# dimmer.net
KiCad netlist of a schematic drawn in EAGLE
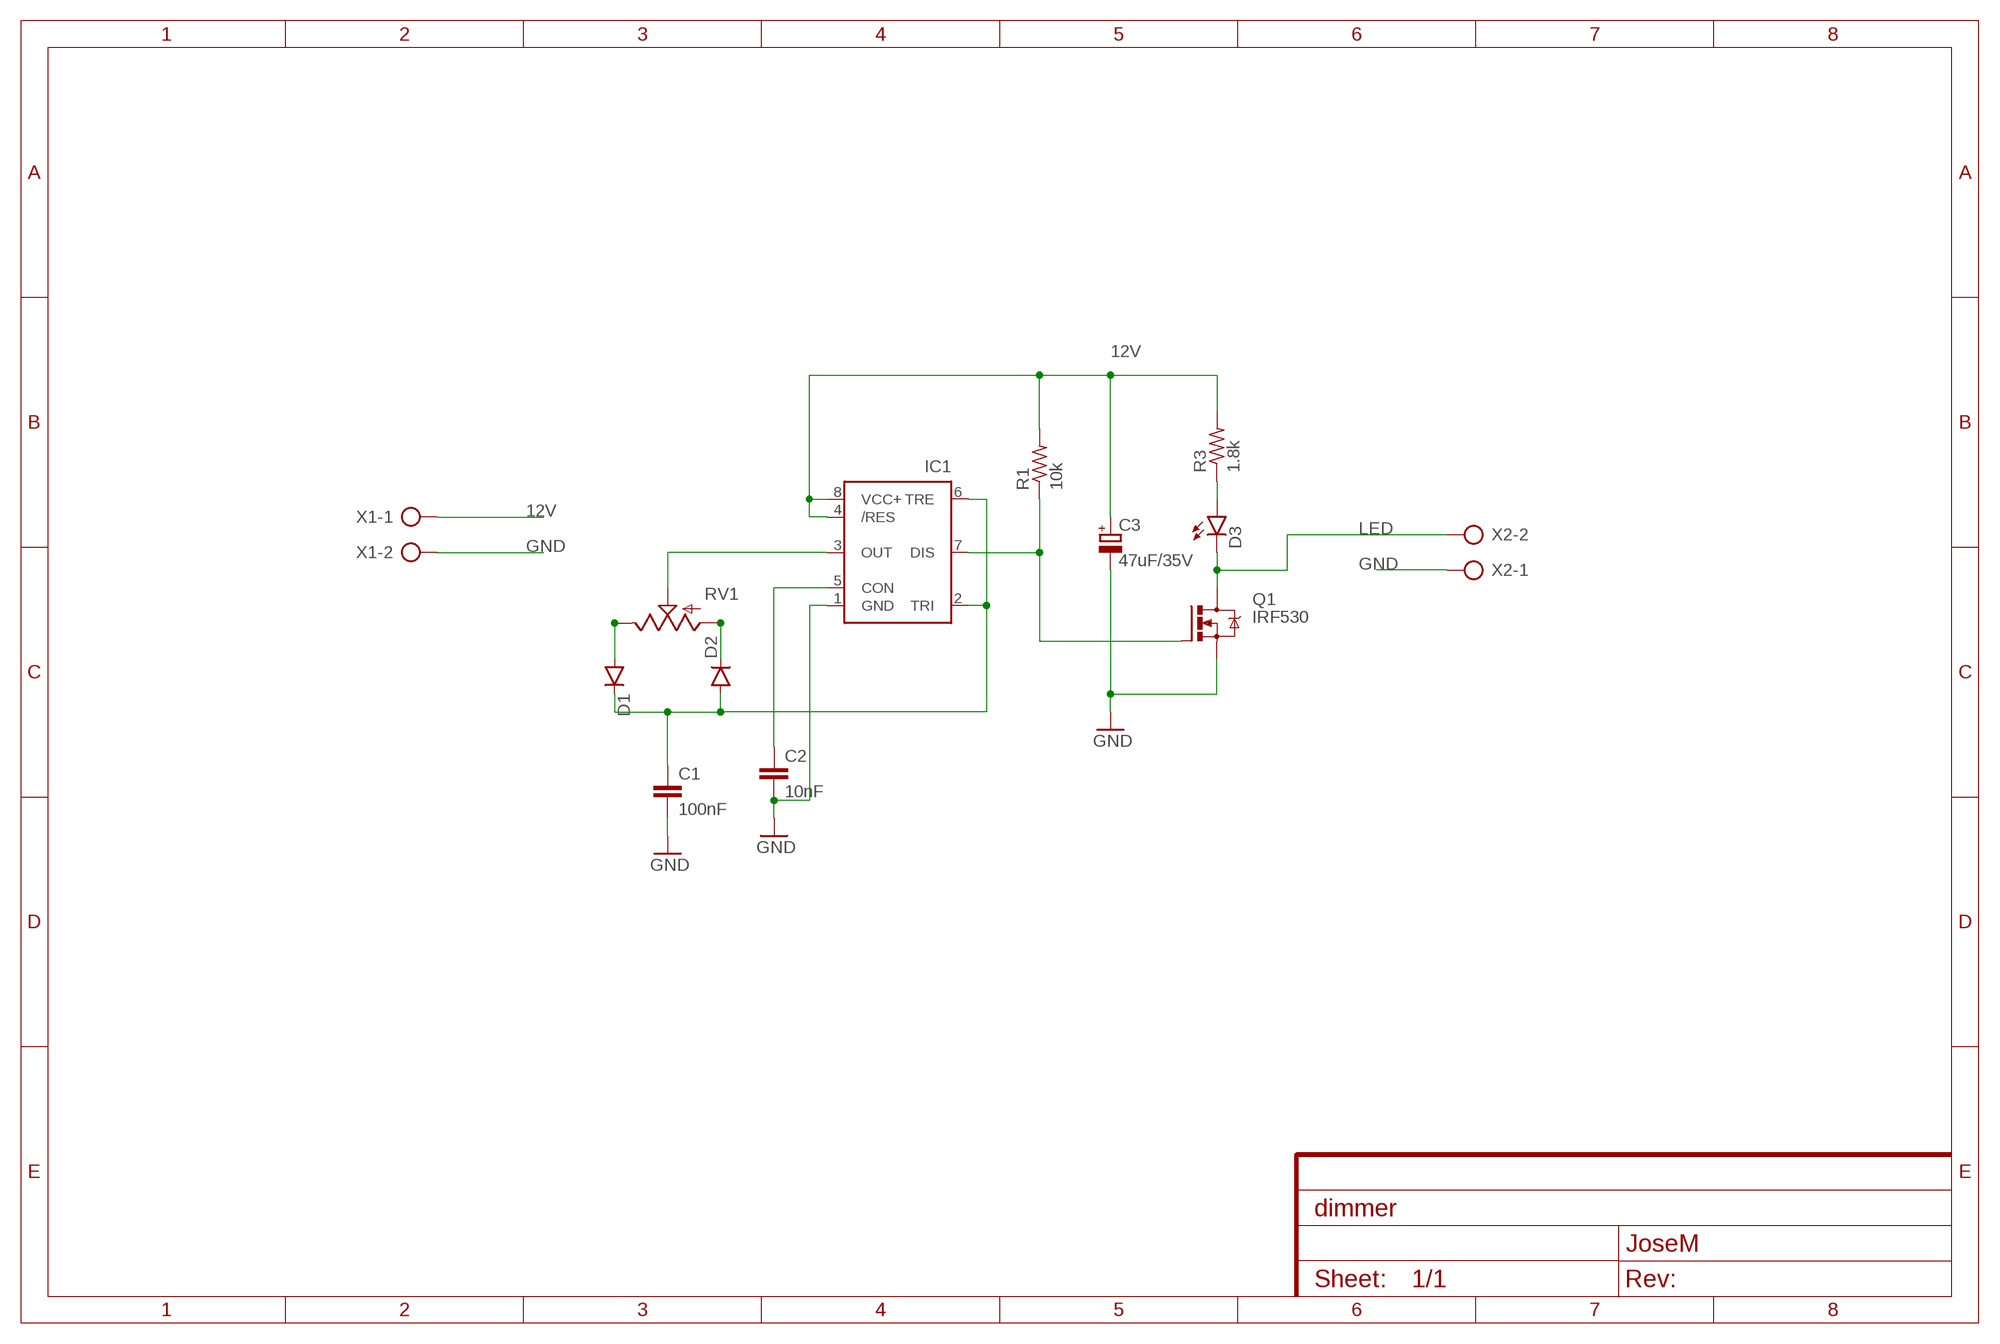
[diagram p0: schematic, sheet 1]

(export (version "E")
  (design (tool "Eeschema 10.0.6"))
  (components
    (comp (ref "C1")
      (value "100nF")
      (footprint "eagle-import:C050-025X075")
      (libsource (lib "eagle-import") (part "C-EU050-025X075"))
    )
    (comp (ref "C2")
      (value "10nF")
      (footprint "eagle-import:C050-025X075")
      (libsource (lib "eagle-import") (part "C-EU050-025X075"))
    )
    (comp (ref "C3")
      (value "47uF/35V")
      (footprint "eagle-import:E2,5-7")
      (libsource (lib "eagle-import") (part "CPOL-EUE2.5-7"))
    )
    (comp (ref "D1")
      (value "DIODE1N4148")
      (footprint "eagle-import:DIODE-1N4148")
      (libsource (lib "eagle-import") (part "DIODE1N4148"))
    )
    (comp (ref "D2")
      (value "DIODE1N4148")
      (footprint "eagle-import:DIODE-1N4148")
      (libsource (lib "eagle-import") (part "DIODE1N4148"))
    )
    (comp (ref "D3")
      (value "LED5MM")
      (footprint "eagle-import:LED5MM")
      (libsource (lib "eagle-import") (part "LED5MM"))
    )
    (comp (ref "IC1")
      (value "NE555P")
      (footprint "eagle-import:DIL-08")
      (fields (field (name "MF") "Arrow Electronics") (field (name "MPN") "NE555N"))
      (libsource (lib "eagle-import") (part "NE555P"))
    )
    (comp (ref "Q1")
      (value "IRF530")
      (footprint "eagle-import:TO220BV")
      (libsource (lib "eagle-import") (part "IRF530"))
    )
    (comp (ref "R1")
      (value "10k")
      (footprint "eagle-import:0207_10")
      (libsource (lib "eagle-import") (part "R-US_0207/10"))
    )
    (comp (ref "R3")
      (value "1.8k")
      (footprint "eagle-import:0207_10")
      (libsource (lib "eagle-import") (part "R-US_0207/10"))
    )
    (comp (ref "RV1")
      (value "POT-RV16AF-20")
      (footprint "eagle-import:POT_ALPHA_RV16AF-20")
      (libsource (lib "eagle-import") (part "POT-RV16AF-20"))
    )
    (comp (ref "X1")
      (value "AK300/2")
      (footprint "eagle-import:AK300_2")
      (libsource (lib "eagle-import") (part "AK300/2"))
    )
    (comp (ref "X2")
      (value "AK300/2")
      (footprint "eagle-import:AK300_2")
      (libsource (lib "eagle-import") (part "AK300/2"))
    )
  )
  (nets
    (net (code "1") (name "/12V") (class "Default")
      (node (ref "C3") (pin "+") (pinfunction "+_+") (pintype "passive"))
      (node (ref "IC1") (pin "4") (pinfunction "/RES_4") (pintype "input"))
      (node (ref "IC1") (pin "8") (pinfunction "VCC+_8") (pintype "power_in"))
      (node (ref "R1") (pin "2") (pinfunction "2_2") (pintype "passive"))
      (node (ref "R3") (pin "2") (pinfunction "2_2") (pintype "passive"))
      (node (ref "X1") (pin "1") (pinfunction "KL_1") (pintype "passive"))
    )
    (net (code "2") (name "/LED") (class "Default")
      (node (ref "D3") (pin "K") (pinfunction "C_K") (pintype "passive"))
      (node (ref "Q1") (pin "D") (pinfunction "D_D") (pintype "passive"))
      (node (ref "X2") (pin "2") (pinfunction "KL_2") (pintype "passive"))
    )
    (net (code "3") (name "GND") (class "Default")
      (node (ref "C1") (pin "2") (pinfunction "2_2") (pintype "passive"))
      (node (ref "C2") (pin "2") (pinfunction "2_2") (pintype "passive"))
      (node (ref "C3") (pin "-") (pinfunction "-_-") (pintype "passive"))
      (node (ref "IC1") (pin "1") (pinfunction "GND_1") (pintype "power_in"))
      (node (ref "Q1") (pin "S") (pinfunction "S_S") (pintype "passive"))
      (node (ref "X1") (pin "2") (pinfunction "KL_2") (pintype "passive"))
      (node (ref "X2") (pin "1") (pinfunction "KL_1") (pintype "passive"))
    )
    (net (code "4") (name "Net-(D3-PadA)") (class "Default")
      (node (ref "D3") (pin "A") (pinfunction "A_A") (pintype "passive"))
      (node (ref "R3") (pin "1") (pinfunction "1_1") (pintype "passive"))
    )
    (net (code "5") (name "Net-(IC1-CON)") (class "Default")
      (node (ref "C2") (pin "1") (pinfunction "1_1") (pintype "passive"))
      (node (ref "IC1") (pin "5") (pinfunction "CON_5") (pintype "input"))
    )
    (net (code "6") (name "Net-(IC1-DIS)") (class "Default")
      (node (ref "IC1") (pin "7") (pinfunction "DIS_7") (pintype "input"))
      (node (ref "Q1") (pin "G") (pinfunction "G_G") (pintype "passive"))
      (node (ref "R1") (pin "1") (pinfunction "1_1") (pintype "passive"))
    )
    (net (code "7") (name "Net-(IC1-OUT)") (class "Default")
      (node (ref "IC1") (pin "3") (pinfunction "OUT_3") (pintype "output"))
      (node (ref "RV1") (pin "2") (pinfunction "S_2") (pintype "passive"))
    )
    (net (code "8") (name "Net-(IC1-TRE)") (class "Default")
      (node (ref "C1") (pin "1") (pinfunction "1_1") (pintype "passive"))
      (node (ref "D1") (pin "C") (pinfunction "C_C") (pintype "passive"))
      (node (ref "D2") (pin "A") (pinfunction "A_A") (pintype "passive"))
      (node (ref "IC1") (pin "2") (pinfunction "TRI_2") (pintype "input"))
      (node (ref "IC1") (pin "6") (pinfunction "TRE_6") (pintype "input"))
    )
    (net (code "9") (name "Net-(RV1-A)") (class "Default")
      (node (ref "D2") (pin "C") (pinfunction "C_C") (pintype "passive"))
      (node (ref "RV1") (pin "1") (pinfunction "A_1") (pintype "passive"))
    )
    (net (code "10") (name "Net-(RV1-E)") (class "Default")
      (node (ref "D1") (pin "A") (pinfunction "A_A") (pintype "passive"))
      (node (ref "RV1") (pin "3") (pinfunction "E_3") (pintype "passive"))
    )
  )
)
